# dron_alaplap.net
KiCad netlist of a schematic drawn in EAGLE
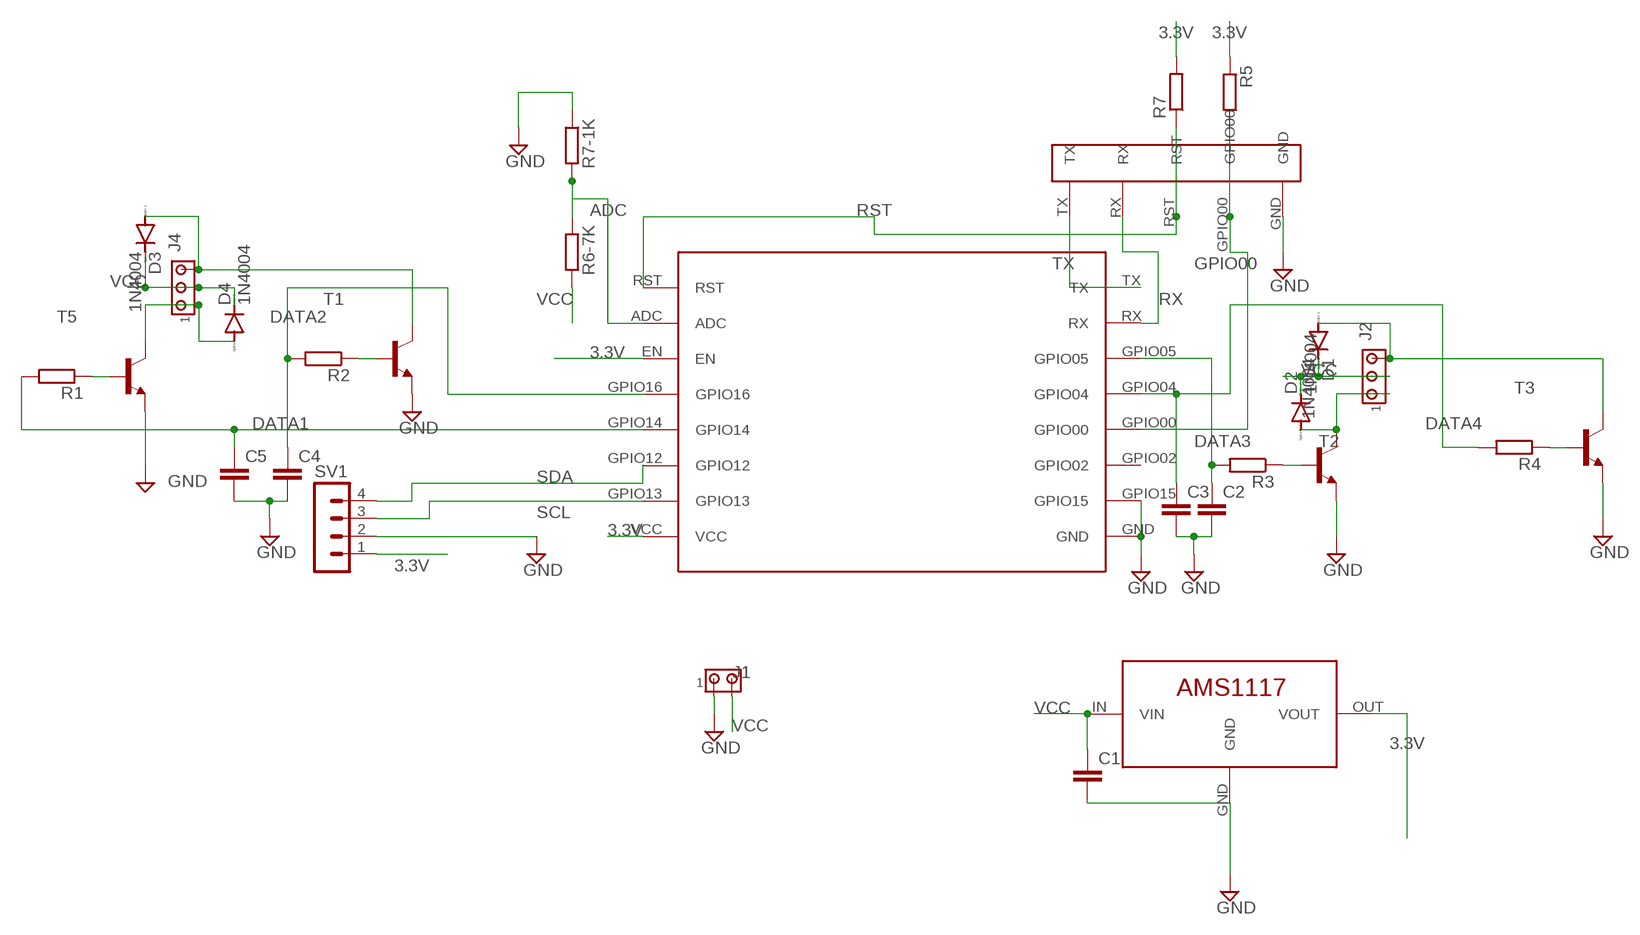
[diagram p0: schematic, sheet 1]

(export (version "E")
  (design (tool "Eeschema 10.0.6"))
  (components
    (comp (ref "C1")
      (value "C-EU025-050X050")
      (footprint "eagle-import:C025-050X050")
      (libsource (lib "eagle-import") (part "C-EU025-050X050"))
    )
    (comp (ref "C2")
      (value "C-EU025-030X050")
      (footprint "eagle-import:C025-030X050")
      (libsource (lib "eagle-import") (part "C-EU025-030X050"))
    )
    (comp (ref "C3")
      (value "C-EU025-030X050")
      (footprint "eagle-import:C025-030X050")
      (libsource (lib "eagle-import") (part "C-EU025-030X050"))
    )
    (comp (ref "C4")
      (value "C-EU025-030X050")
      (footprint "eagle-import:C025-030X050")
      (libsource (lib "eagle-import") (part "C-EU025-030X050"))
    )
    (comp (ref "C5")
      (value "C-EU050-025X075")
      (footprint "eagle-import:C050-025X075")
      (libsource (lib "eagle-import") (part "C-EU050-025X075"))
    )
    (comp (ref "D1")
      (value "1N4004")
      (footprint "eagle-import:DO41-10")
      (libsource (lib "eagle-import") (part "1N4004"))
    )
    (comp (ref "D2")
      (value "1N4004")
      (footprint "eagle-import:DO41-10")
      (libsource (lib "eagle-import") (part "1N4004"))
    )
    (comp (ref "D3")
      (value "1N4004")
      (footprint "eagle-import:DO41-10")
      (libsource (lib "eagle-import") (part "1N4004"))
    )
    (comp (ref "D4")
      (value "1N4004")
      (footprint "eagle-import:DO41-10")
      (libsource (lib "eagle-import") (part "1N4004"))
    )
    (comp (ref "J1")
      (value "MTA02-156")
      (footprint "eagle-import:1X2MTA")
      (libsource (lib "eagle-import") (part "MTA02-156"))
    )
    (comp (ref "J2")
      (value "MTA03-156")
      (footprint "eagle-import:1X3MTA")
      (libsource (lib "eagle-import") (part "MTA03-156"))
    )
    (comp (ref "J4")
      (value "MTA03-156")
      (footprint "eagle-import:1X3MTA")
      (libsource (lib "eagle-import") (part "MTA03-156"))
    )
    (comp (ref "R1")
      (value "R-EU_0207/12")
      (footprint "eagle-import:0207_12")
      (libsource (lib "eagle-import") (part "R-EU_0207/12"))
    )
    (comp (ref "R2")
      (value "R-EU_0207/12")
      (footprint "eagle-import:0207_12")
      (libsource (lib "eagle-import") (part "R-EU_0207/12"))
    )
    (comp (ref "R3")
      (value "R-EU_0207/12")
      (footprint "eagle-import:0207_12")
      (libsource (lib "eagle-import") (part "R-EU_0207/12"))
    )
    (comp (ref "R4")
      (value "R-EU_0207/12")
      (footprint "eagle-import:0207_12")
      (libsource (lib "eagle-import") (part "R-EU_0207/12"))
    )
    (comp (ref "R5")
      (value "R-EU_0207/12")
      (footprint "eagle-import:0207_12")
      (libsource (lib "eagle-import") (part "R-EU_0207/12"))
    )
    (comp (ref "R6-7K")
      (value "R-EU_0207/12")
      (footprint "eagle-import:0207_12")
      (libsource (lib "eagle-import") (part "R-EU_0207/12"))
    )
    (comp (ref "R7")
      (value "R-EU_0207/15")
      (footprint "eagle-import:0207_15")
      (libsource (lib "eagle-import") (part "R-EU_0207/15"))
    )
    (comp (ref "R7-1K")
      (value "R-EU_0207/12")
      (footprint "eagle-import:0207_12")
      (libsource (lib "eagle-import") (part "R-EU_0207/12"))
    )
    (comp (ref "SV1")
      (value "MA04-1")
      (footprint "eagle-import:MA04-1")
      (libsource (lib "eagle-import") (part "MA04-1"))
    )
    (comp (ref "T1")
      (value "2N2222-NPN-TO92-EBC")
      (footprint "eagle-import:TO92-EBC")
      (libsource (lib "eagle-import") (part "-NPN-TO92-EBC2N2222"))
    )
    (comp (ref "T2")
      (value "2N2222-NPN-TO92-EBC")
      (footprint "eagle-import:TO92-EBC")
      (libsource (lib "eagle-import") (part "-NPN-TO92-EBC2N2222"))
    )
    (comp (ref "T3")
      (value "2N2222-NPN-TO92-EBC")
      (footprint "eagle-import:TO92-EBC")
      (libsource (lib "eagle-import") (part "-NPN-TO92-EBC2N2222"))
    )
    (comp (ref "T5")
      (value "2N2222-NPN-TO92-EBC")
      (footprint "eagle-import:TO92-EBC")
      (libsource (lib "eagle-import") (part "-NPN-TO92-EBC2N2222"))
    )
    (comp (ref "U$1")
      (value "AMS1117")
      (footprint "eagle-import:AMS1117")
      (libsource (lib "eagle-import") (part "AMS1117"))
    )
    (comp (ref "U$2")
      (value "ESP8266")
      (footprint "eagle-import:ESP8266")
      (libsource (lib "eagle-import") (part "ESP8266"))
    )
    (comp (ref "U$3")
      (value "PIN")
      (footprint "eagle-import:PIN")
      (libsource (lib "eagle-import") (part "PIN"))
    )
  )
  (nets
    (net (code "1") (name "/3.3V") (class "Default")
      (node (ref "R5") (pin "1") (pinfunction "1_1") (pintype "passive"))
      (node (ref "R7") (pin "2") (pinfunction "2_2") (pintype "passive"))
      (node (ref "SV1") (pin "1") (pinfunction "1_1") (pintype "passive"))
      (node (ref "U$1") (pin "OUT") (pinfunction "VOUT_OUT") (pintype "bidirectional"))
      (node (ref "U$2") (pin "EN") (pinfunction "EN_EN") (pintype "bidirectional"))
      (node (ref "U$2") (pin "VCC") (pinfunction "VCC_VCC") (pintype "bidirectional"))
    )
    (net (code "2") (name "/ADC") (class "Default")
      (node (ref "R6-7K") (pin "1") (pinfunction "1_1") (pintype "passive"))
      (node (ref "R7-1K") (pin "2") (pinfunction "2_2") (pintype "passive"))
      (node (ref "U$2") (pin "ADC") (pinfunction "ADC_ADC") (pintype "bidirectional"))
    )
    (net (code "3") (name "/DATA1") (class "Default")
      (node (ref "C5") (pin "1") (pinfunction "1_1") (pintype "passive"))
      (node (ref "R1") (pin "2") (pinfunction "2_2") (pintype "passive"))
      (node (ref "U$2") (pin "GPIO14") (pinfunction "GPIO14_GPIO14") (pintype "bidirectional"))
    )
    (net (code "4") (name "/DATA2") (class "Default")
      (node (ref "C4") (pin "1") (pinfunction "1_1") (pintype "passive"))
      (node (ref "R2") (pin "2") (pinfunction "2_2") (pintype "passive"))
      (node (ref "U$2") (pin "GPIO16") (pinfunction "GPIO16_GPIO16") (pintype "bidirectional"))
    )
    (net (code "5") (name "/DATA3") (class "Default")
      (node (ref "C2") (pin "1") (pinfunction "1_1") (pintype "passive"))
      (node (ref "R3") (pin "2") (pinfunction "2_2") (pintype "passive"))
      (node (ref "U$2") (pin "GPIO05") (pinfunction "GPIO05_GPIO05") (pintype "bidirectional"))
    )
    (net (code "6") (name "/DATA4") (class "Default")
      (node (ref "C3") (pin "1") (pinfunction "1_1") (pintype "passive"))
      (node (ref "R4") (pin "2") (pinfunction "2_2") (pintype "passive"))
      (node (ref "U$2") (pin "GPIO04") (pinfunction "GPIO04_GPIO04") (pintype "bidirectional"))
    )
    (net (code "7") (name "/GPIO00") (class "Default")
      (node (ref "R5") (pin "2") (pinfunction "2_2") (pintype "passive"))
      (node (ref "U$2") (pin "GPIO00") (pinfunction "GPIO00_GPIO00") (pintype "bidirectional"))
      (node (ref "U$3") (pin "GPIO00") (pinfunction "GPIO00_GPIO00") (pintype "bidirectional"))
    )
    (net (code "8") (name "/RST") (class "Default")
      (node (ref "R7") (pin "1") (pinfunction "1_1") (pintype "passive"))
      (node (ref "U$2") (pin "RST") (pinfunction "RST_RST") (pintype "bidirectional"))
      (node (ref "U$3") (pin "RST") (pinfunction "RST_RST") (pintype "bidirectional"))
    )
    (net (code "9") (name "/RX") (class "Default")
      (node (ref "U$2") (pin "RX") (pinfunction "RX_RX") (pintype "bidirectional"))
      (node (ref "U$3") (pin "RX") (pinfunction "RX_RX") (pintype "bidirectional"))
    )
    (net (code "10") (name "/SCL") (class "Default")
      (node (ref "SV1") (pin "3") (pinfunction "3_3") (pintype "passive"))
      (node (ref "U$2") (pin "GPIO13") (pinfunction "GPIO13_GPIO13") (pintype "bidirectional"))
    )
    (net (code "11") (name "/SDA") (class "Default")
      (node (ref "SV1") (pin "4") (pinfunction "4_4") (pintype "passive"))
      (node (ref "U$2") (pin "GPIO12") (pinfunction "GPIO12_GPIO12") (pintype "bidirectional"))
    )
    (net (code "12") (name "/TX") (class "Default")
      (node (ref "U$2") (pin "TX") (pinfunction "TX_TX") (pintype "bidirectional"))
      (node (ref "U$3") (pin "TX") (pinfunction "TX_TX") (pintype "bidirectional"))
    )
    (net (code "13") (name "/VCC") (class "Default")
      (node (ref "C1") (pin "1") (pinfunction "1_1") (pintype "passive"))
      (node (ref "D1") (pin "C") (pinfunction "C_C") (pintype "passive"))
      (node (ref "D2") (pin "C") (pinfunction "C_C") (pintype "passive"))
      (node (ref "D3") (pin "C") (pinfunction "C_C") (pintype "passive"))
      (node (ref "D4") (pin "C") (pinfunction "C_C") (pintype "passive"))
      (node (ref "J1") (pin "2") (pinfunction "2_2") (pintype "passive"))
      (node (ref "J2") (pin "2") (pinfunction "2_2") (pintype "passive"))
      (node (ref "J4") (pin "2") (pinfunction "2_2") (pintype "passive"))
      (node (ref "R6-7K") (pin "2") (pinfunction "2_2") (pintype "passive"))
      (node (ref "U$1") (pin "IN") (pinfunction "VIN_IN") (pintype "bidirectional"))
    )
    (net (code "14") (name "GND") (class "Default")
      (node (ref "C1") (pin "2") (pinfunction "2_2") (pintype "passive"))
      (node (ref "C2") (pin "2") (pinfunction "2_2") (pintype "passive"))
      (node (ref "C3") (pin "2") (pinfunction "2_2") (pintype "passive"))
      (node (ref "C4") (pin "2") (pinfunction "2_2") (pintype "passive"))
      (node (ref "C5") (pin "2") (pinfunction "2_2") (pintype "passive"))
      (node (ref "J1") (pin "1") (pinfunction "1_1") (pintype "passive"))
      (node (ref "R7-1K") (pin "1") (pinfunction "1_1") (pintype "passive"))
      (node (ref "SV1") (pin "2") (pinfunction "2_2") (pintype "passive"))
      (node (ref "T1") (pin "E") (pinfunction "E_E") (pintype "passive"))
      (node (ref "T2") (pin "E") (pinfunction "E_E") (pintype "passive"))
      (node (ref "T3") (pin "E") (pinfunction "E_E") (pintype "passive"))
      (node (ref "T5") (pin "E") (pinfunction "E_E") (pintype "passive"))
      (node (ref "U$1") (pin "GND") (pinfunction "GND_GND") (pintype "bidirectional"))
      (node (ref "U$2") (pin "GND") (pinfunction "GND_GND") (pintype "bidirectional"))
      (node (ref "U$2") (pin "GPIO15") (pinfunction "GPIO15_GPIO15") (pintype "bidirectional"))
      (node (ref "U$3") (pin "GND") (pinfunction "GND_GND") (pintype "bidirectional"))
    )
    (net (code "15") (name "Net-(D1-PadA)") (class "Default")
      (node (ref "D1") (pin "A") (pinfunction "A_A") (pintype "passive"))
      (node (ref "J2") (pin "3") (pinfunction "3_3") (pintype "passive"))
      (node (ref "T3") (pin "C") (pinfunction "C_C") (pintype "passive"))
    )
    (net (code "16") (name "Net-(D2-PadA)") (class "Default")
      (node (ref "D2") (pin "A") (pinfunction "A_A") (pintype "passive"))
      (node (ref "J2") (pin "1") (pinfunction "1_1") (pintype "passive"))
      (node (ref "T2") (pin "C") (pinfunction "C_C") (pintype "passive"))
    )
    (net (code "17") (name "Net-(D3-PadA)") (class "Default")
      (node (ref "D3") (pin "A") (pinfunction "A_A") (pintype "passive"))
      (node (ref "J4") (pin "3") (pinfunction "3_3") (pintype "passive"))
      (node (ref "T1") (pin "C") (pinfunction "C_C") (pintype "passive"))
    )
    (net (code "18") (name "Net-(D4-PadA)") (class "Default")
      (node (ref "D4") (pin "A") (pinfunction "A_A") (pintype "passive"))
      (node (ref "J4") (pin "1") (pinfunction "1_1") (pintype "passive"))
      (node (ref "T5") (pin "C") (pinfunction "C_C") (pintype "passive"))
    )
    (net (code "19") (name "Net-(R1-Pad1)") (class "Default")
      (node (ref "R1") (pin "1") (pinfunction "1_1") (pintype "passive"))
      (node (ref "T5") (pin "B") (pinfunction "B_B") (pintype "passive"))
    )
    (net (code "20") (name "Net-(R2-Pad1)") (class "Default")
      (node (ref "R2") (pin "1") (pinfunction "1_1") (pintype "passive"))
      (node (ref "T1") (pin "B") (pinfunction "B_B") (pintype "passive"))
    )
    (net (code "21") (name "Net-(R3-Pad1)") (class "Default")
      (node (ref "R3") (pin "1") (pinfunction "1_1") (pintype "passive"))
      (node (ref "T2") (pin "B") (pinfunction "B_B") (pintype "passive"))
    )
    (net (code "22") (name "Net-(R4-Pad1)") (class "Default")
      (node (ref "R4") (pin "1") (pinfunction "1_1") (pintype "passive"))
      (node (ref "T3") (pin "B") (pinfunction "B_B") (pintype "passive"))
    )
    (net (code "23") (name "unconnected-(U$2-PadGPIO02)") (class "Default")
      (node (ref "U$2") (pin "GPIO02") (pinfunction "GPIO02_GPIO02") (pintype "bidirectional"))
    )
  )
)
